# Sheet2.net
KiCad netlist of a schematic drawn in Altium Designer
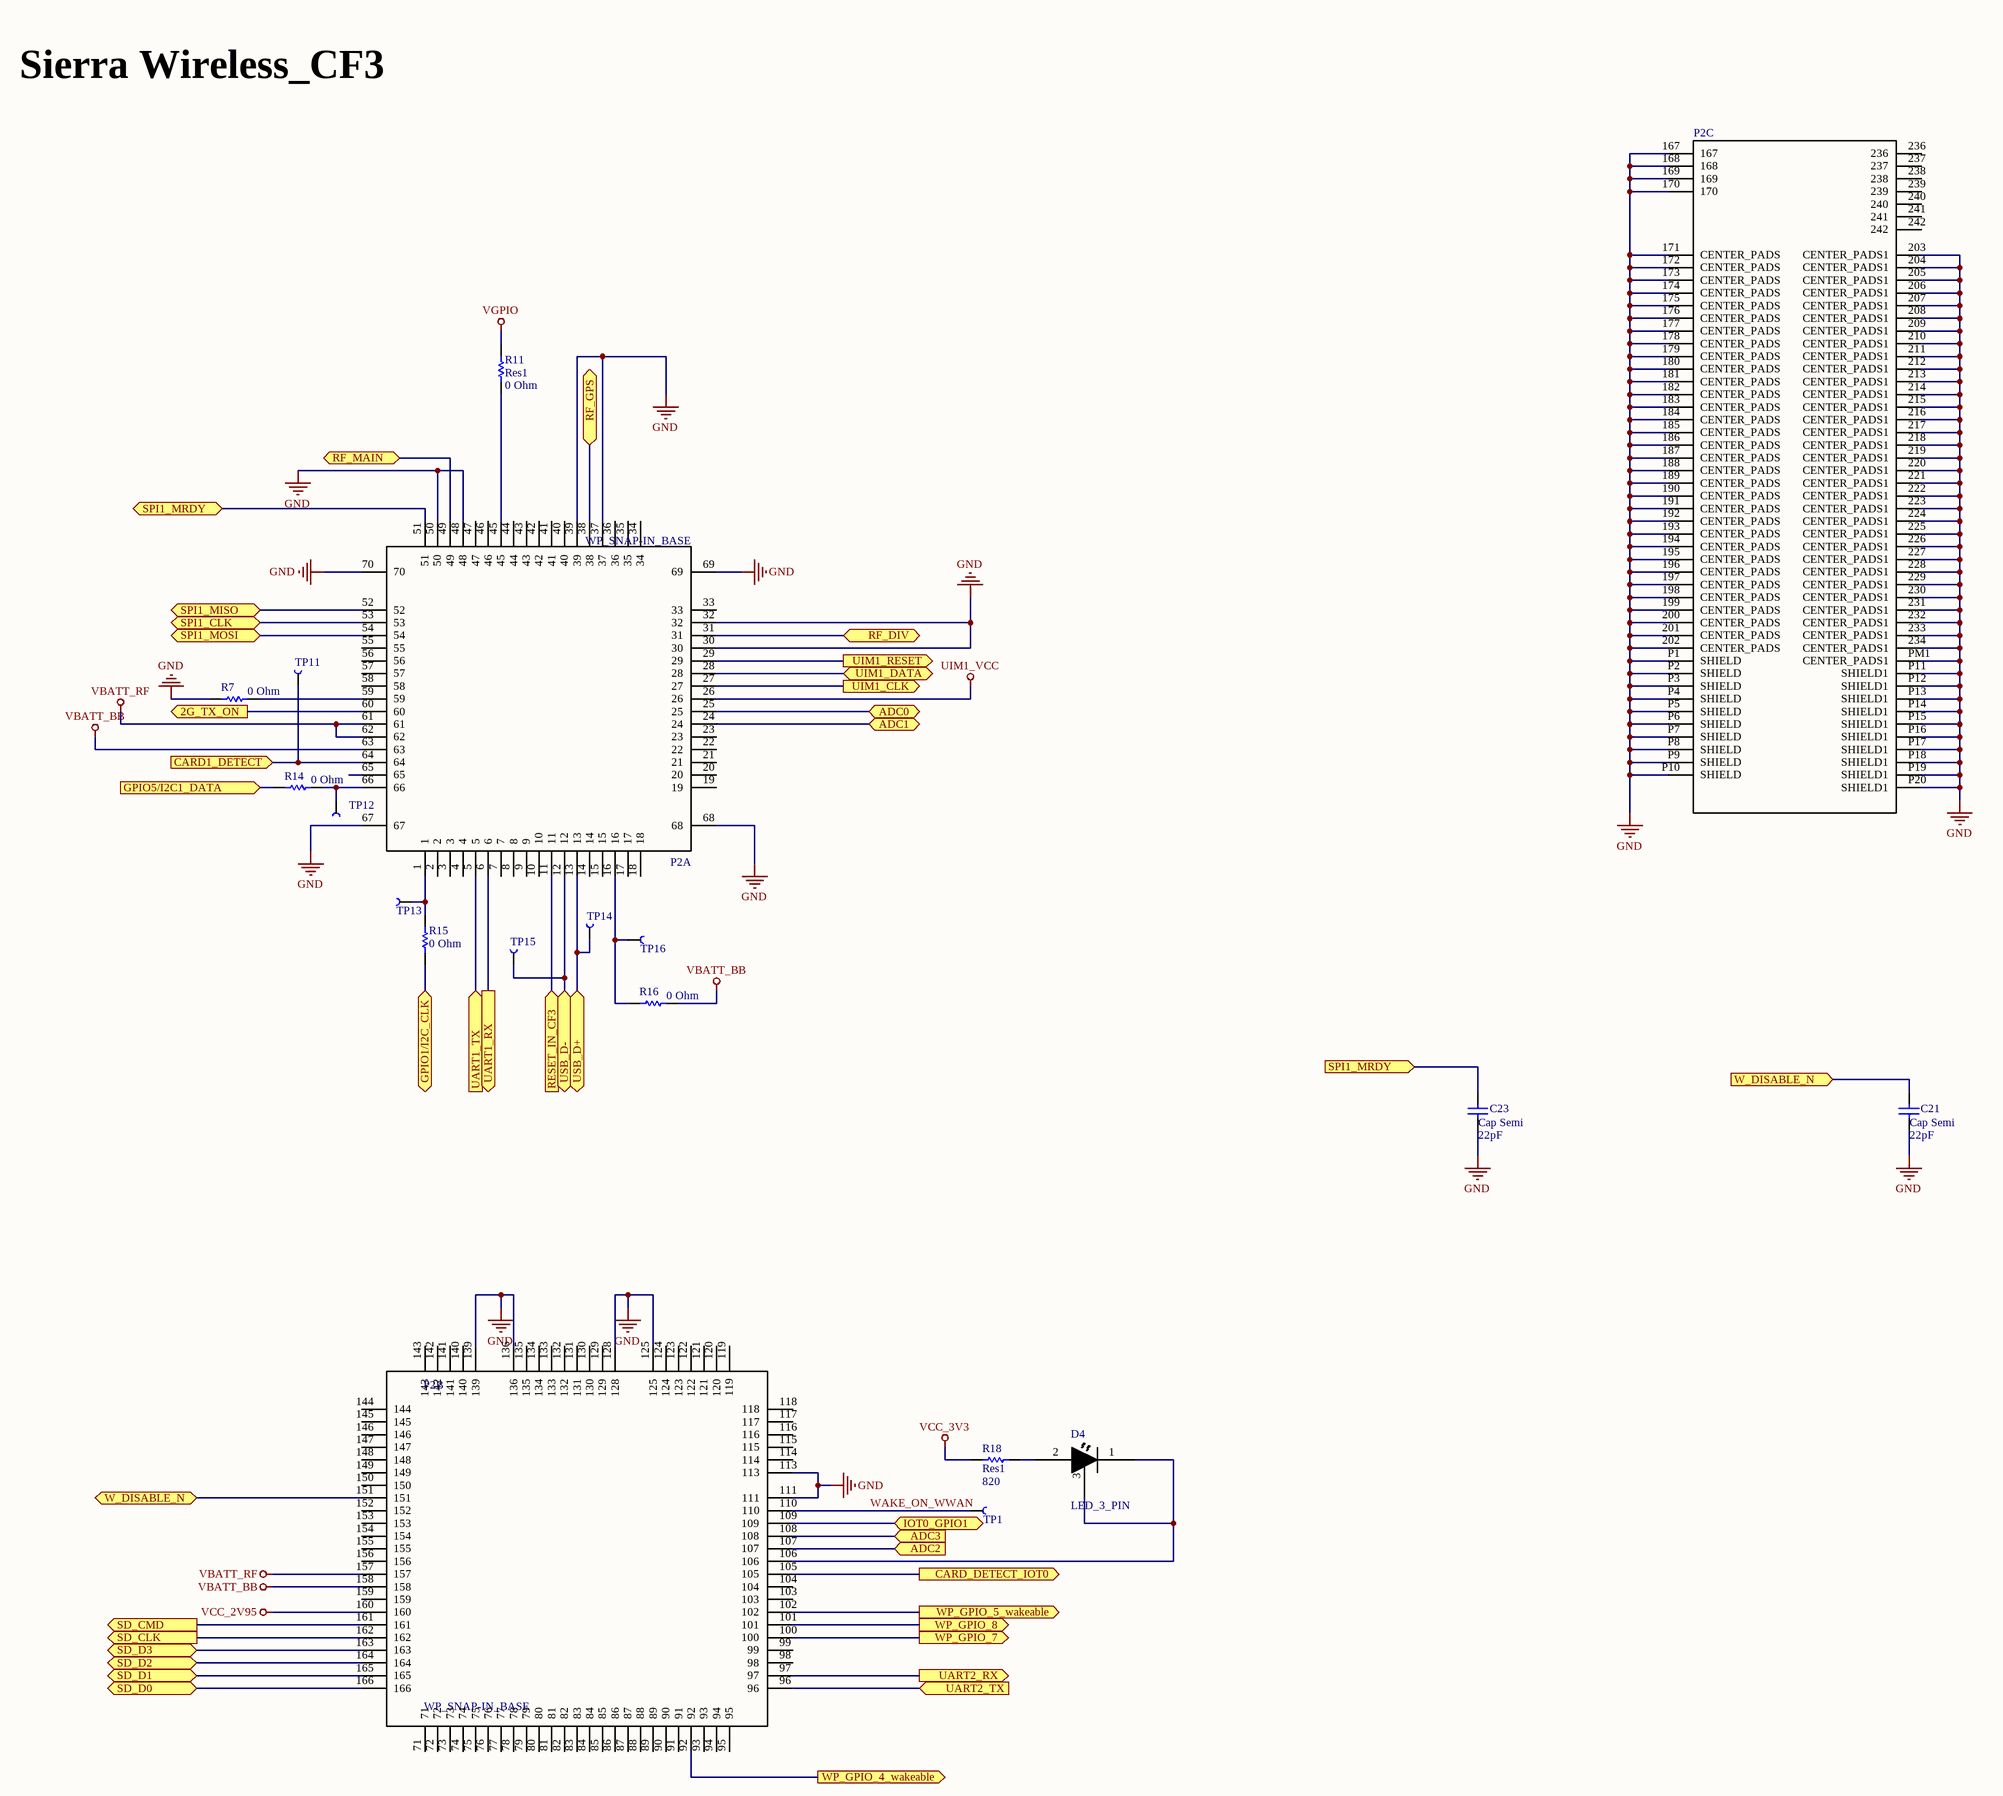
[diagram p0: Sheet2.SchDoc]

(export (version "E")
  (design (tool "Eeschema 10.0.6"))
  (components
    (comp (ref "C21")
      (value "Cap Semi")
      (footprint "CAP 0402/1005")
      (description "CAP CER 22PF 50V NP0 0402")
      (fields (field (name "PART NUMBER") "UMK105CG220JV-F") (field (name "ALTIUM_VALUE") "22pF"))
      (libsource (lib "Miscellaneous Devices") (part "Cap Semi"))
    )
    (comp (ref "C23")
      (value "Cap Semi")
      (footprint "CAP 0402/1005")
      (description "CAP CER 22PF 50V NP0 0402")
      (fields (field (name "PART NUMBER") "UMK105CG220JV-F") (field (name "ALTIUM_VALUE") "22pF"))
      (libsource (lib "Miscellaneous Devices") (part "Cap Semi"))
    )
    (comp (ref "D4")
      (value "LED_3_PIN")
      (footprint "LED_3_PIN")
      (description "Yellow-Green 573nm LED Indication - Discrete 2V 2-SMD, No Lead")
      (fields (field (name "PART NUMBER") "12-21SYGC/S530-E2/TR8"))
      (libsource (lib "LED_3_PIN") (part "LED_3_PIN"))
    )
    (comp (ref "P2")
      (value "WP_SNAP-IN_BASE")
      (footprint "*SIERRA_WP_SNAP-IN_BASE_WP_SNAP-IN_BASE(Primary)")
      (description "Snap-In Socket Base For Wp Series Mcu")
      (fields (field (name "PART NUMBER") "WP SNAP-IN BASE") (field (name "MF") "Sierra Wireless"))
      (libsource (lib "WP_SNAP-IN_BASE") (part "WP_SNAP-IN_BASE"))
    )
    (comp (ref "R7")
      (value "0 Ohm")
      (footprint "RES 0402/1005")
      (description "0 Ohms Jumper  Chip Resistor 0402 (1005 Metric) Automotive AEC-Q200 Metal Element")
      (fields (field (name "PART NUMBER") "RK73Z1ETTP") (field (name "Comment") "Res1"))
      (libsource (lib "Miscellaneous Devices") (part "Res1"))
    )
    (comp (ref "R11")
      (value "Res1")
      (footprint "RES 0402/1005")
      (description "0 Ohms Jumper  Chip Resistor 0402 (1005 Metric) Automotive AEC-Q200 Metal Element")
      (fields (field (name "PART NUMBER") "RK73Z1ETTP") (field (name "ALTIUM_VALUE") "0 Ohm"))
      (libsource (lib "Miscellaneous Devices") (part "Res1"))
    )
    (comp (ref "R14")
      (value "0 Ohm")
      (footprint "RES 0402/1005")
      (description "0 Ohms Jumper  Chip Resistor 0402 (1005 Metric) Automotive AEC-Q200 Metal Element")
      (fields (field (name "PART NUMBER") "RK73Z1ETTP") (field (name "Comment") "Res1"))
      (libsource (lib "Miscellaneous Devices") (part "Res1"))
    )
    (comp (ref "R15")
      (value "0 Ohm")
      (footprint "RES 0402/1005")
      (description "0 Ohms Jumper  Chip Resistor 0402 (1005 Metric) Automotive AEC-Q200 Metal Element")
      (fields (field (name "PART NUMBER") "RK73Z1ETTP") (field (name "Comment") "Res1"))
      (libsource (lib "Miscellaneous Devices") (part "Res1"))
    )
    (comp (ref "R16")
      (value "0 Ohm")
      (footprint "RES 0402/1005")
      (description "0 Ohms Jumper  Chip Resistor 0402 (1005 Metric) Automotive AEC-Q200 Metal Element")
      (fields (field (name "PART NUMBER") "RK73Z1ETTP") (field (name "Comment") "Res1"))
      (libsource (lib "Miscellaneous Devices") (part "Res1"))
    )
    (comp (ref "R18")
      (value "Res1")
      (footprint "RES 0402/1005")
      (description "820 Ohms ±5% 0.1W, 1/10W Chip Resistor 0402 (1005 Metric) Automotive AEC-Q200 Thick Film")
      (fields (field (name "PART NUMBER") "RK73B1ETTP821J") (field (name "ALTIUM_VALUE") "820"))
      (libsource (lib "Miscellaneous Devices") (part "Res1"))
    )
    (comp (ref "TP1")
      (value "TestPoint")
      (footprint "TestPoint")
      (libsource (lib "TestPoint") (part "TestPoint"))
    )
    (comp (ref "TP11")
      (value "TestPoint")
      (footprint "TestPoint")
      (libsource (lib "TestPoint") (part "TestPoint"))
    )
    (comp (ref "TP12")
      (value "TestPoint")
      (footprint "TestPoint")
      (libsource (lib "TestPoint") (part "TestPoint"))
    )
    (comp (ref "TP13")
      (value "TestPoint")
      (footprint "TestPoint")
      (libsource (lib "TestPoint") (part "TestPoint"))
    )
    (comp (ref "TP14")
      (value "TestPoint")
      (footprint "TestPoint")
      (libsource (lib "TestPoint") (part "TestPoint"))
    )
    (comp (ref "TP15")
      (value "TestPoint")
      (footprint "TestPoint")
      (libsource (lib "TestPoint") (part "TestPoint"))
    )
    (comp (ref "TP16")
      (value "TestPoint")
      (footprint "TestPoint")
      (libsource (lib "TestPoint") (part "TestPoint"))
    )
  )
  (nets
    (net (code "1") (name "/2G_TX_ON") (class "Default")
      (node (ref "P2") (pin "60") (pinfunction "60_60") (pintype "passive"))
    )
    (net (code "2") (name "/ADC0") (class "Default")
      (node (ref "P2") (pin "25") (pinfunction "25_25") (pintype "passive"))
    )
    (net (code "3") (name "/ADC1") (class "Default")
      (node (ref "P2") (pin "24") (pinfunction "24_24") (pintype "passive"))
    )
    (net (code "4") (name "/ADC2") (class "Default")
      (node (ref "P2") (pin "107") (pinfunction "107_107") (pintype "passive"))
    )
    (net (code "5") (name "/ADC3") (class "Default")
      (node (ref "P2") (pin "108") (pinfunction "108_108") (pintype "passive"))
    )
    (net (code "6") (name "/CARD1_DETECT") (class "Default")
      (node (ref "P2") (pin "64") (pinfunction "64_64") (pintype "passive"))
      (node (ref "TP11") (pin "1") (pinfunction "TP_1") (pintype "passive"))
    )
    (net (code "7") (name "/CARD_DETECT_IOT0") (class "Default")
      (node (ref "P2") (pin "105") (pinfunction "105_105") (pintype "passive"))
    )
    (net (code "8") (name "/GPIO1{slash}I2C_CLK") (class "Default")
      (node (ref "R15") (pin "2") (pinfunction "2_2") (pintype "passive"))
    )
    (net (code "9") (name "/GPIO5{slash}I2C1_DATA") (class "Default")
      (node (ref "R14") (pin "2") (pinfunction "2_2") (pintype "passive"))
    )
    (net (code "10") (name "/IOT0_GPIO1") (class "Default")
      (node (ref "P2") (pin "109") (pinfunction "109_109") (pintype "passive"))
    )
    (net (code "11") (name "/RESET_IN_CF3") (class "Default")
      (node (ref "P2") (pin "11") (pinfunction "11_11") (pintype "passive"))
    )
    (net (code "12") (name "/RF_DIV") (class "Default")
      (node (ref "P2") (pin "31") (pinfunction "31_31") (pintype "passive"))
    )
    (net (code "13") (name "/RF_GPS") (class "Default")
      (node (ref "P2") (pin "38") (pinfunction "38_38") (pintype "passive"))
    )
    (net (code "14") (name "/RF_MAIN") (class "Default")
      (node (ref "P2") (pin "49") (pinfunction "49_49") (pintype "passive"))
    )
    (net (code "15") (name "/SD_CLK") (class "Default")
      (node (ref "P2") (pin "162") (pinfunction "162_162") (pintype "passive"))
    )
    (net (code "16") (name "/SD_CMD") (class "Default")
      (node (ref "P2") (pin "161") (pinfunction "161_161") (pintype "passive"))
    )
    (net (code "17") (name "/SD_D0") (class "Default")
      (node (ref "P2") (pin "166") (pinfunction "166_166") (pintype "passive"))
    )
    (net (code "18") (name "/SD_D1") (class "Default")
      (node (ref "P2") (pin "165") (pinfunction "165_165") (pintype "passive"))
    )
    (net (code "19") (name "/SD_D2") (class "Default")
      (node (ref "P2") (pin "164") (pinfunction "164_164") (pintype "passive"))
    )
    (net (code "20") (name "/SD_D3") (class "Default")
      (node (ref "P2") (pin "163") (pinfunction "163_163") (pintype "passive"))
    )
    (net (code "21") (name "/SPI1_CLK") (class "Default")
      (node (ref "P2") (pin "53") (pinfunction "53_53") (pintype "passive"))
    )
    (net (code "22") (name "/SPI1_MISO") (class "Default")
      (node (ref "P2") (pin "52") (pinfunction "52_52") (pintype "passive"))
    )
    (net (code "23") (name "/SPI1_MOSI") (class "Default")
      (node (ref "P2") (pin "54") (pinfunction "54_54") (pintype "passive"))
    )
    (net (code "24") (name "/SPI1_MRDY") (class "Default")
      (node (ref "C23") (pin "2") (pinfunction "2_2") (pintype "passive"))
      (node (ref "P2") (pin "51") (pinfunction "51_51") (pintype "passive"))
    )
    (net (code "25") (name "/UART1_RX") (class "Default")
      (node (ref "P2") (pin "6") (pinfunction "6_6") (pintype "passive"))
    )
    (net (code "26") (name "/UART1_TX") (class "Default")
      (node (ref "P2") (pin "5") (pinfunction "5_5") (pintype "passive"))
    )
    (net (code "27") (name "/UART2_RX") (class "Default")
      (node (ref "P2") (pin "97") (pinfunction "97_97") (pintype "passive"))
    )
    (net (code "28") (name "/UART2_TX") (class "Default")
      (node (ref "P2") (pin "96") (pinfunction "96_96") (pintype "passive"))
    )
    (net (code "29") (name "/UIM1_CLK") (class "Default")
      (node (ref "P2") (pin "27") (pinfunction "27_27") (pintype "passive"))
    )
    (net (code "30") (name "/UIM1_DATA") (class "Default")
      (node (ref "P2") (pin "28") (pinfunction "28_28") (pintype "passive"))
    )
    (net (code "31") (name "/UIM1_RESET") (class "Default")
      (node (ref "P2") (pin "29") (pinfunction "29_29") (pintype "passive"))
    )
    (net (code "32") (name "/USB_D+") (class "Default")
      (node (ref "P2") (pin "13") (pinfunction "13_13") (pintype "passive"))
      (node (ref "TP14") (pin "1") (pinfunction "TP_1") (pintype "passive"))
    )
    (net (code "33") (name "/USB_D-") (class "Default")
      (node (ref "P2") (pin "12") (pinfunction "12_12") (pintype "passive"))
      (node (ref "TP15") (pin "1") (pinfunction "TP_1") (pintype "passive"))
    )
    (net (code "34") (name "/WAKE_ON_WWAN") (class "Default")
      (node (ref "P2") (pin "110") (pinfunction "110_110") (pintype "passive"))
      (node (ref "TP1") (pin "1") (pinfunction "TP_1") (pintype "passive"))
    )
    (net (code "35") (name "/WP_GPIO_4_wakeable") (class "Default")
      (node (ref "P2") (pin "92") (pinfunction "92_92") (pintype "passive"))
    )
    (net (code "36") (name "/WP_GPIO_5_wakeable") (class "Default")
      (node (ref "P2") (pin "102") (pinfunction "102_102") (pintype "passive"))
    )
    (net (code "37") (name "/WP_GPIO_7") (class "Default")
      (node (ref "P2") (pin "100") (pinfunction "100_100") (pintype "passive"))
    )
    (net (code "38") (name "/WP_GPIO_8") (class "Default")
      (node (ref "P2") (pin "101") (pinfunction "101_101") (pintype "passive"))
    )
    (net (code "39") (name "/W_DISABLE_N") (class "Default")
      (node (ref "C21") (pin "2") (pinfunction "2_2") (pintype "passive"))
      (node (ref "P2") (pin "151") (pinfunction "151_151") (pintype "passive"))
    )
    (net (code "40") (name "GND") (class "Default")
      (node (ref "C21") (pin "1") (pinfunction "1_1") (pintype "passive"))
      (node (ref "C23") (pin "1") (pinfunction "1_1") (pintype "passive"))
      (node (ref "P2") (pin "111") (pinfunction "111_111") (pintype "passive"))
      (node (ref "P2") (pin "113") (pinfunction "113_113") (pintype "passive"))
      (node (ref "P2") (pin "125") (pinfunction "125_125") (pintype "passive"))
      (node (ref "P2") (pin "128") (pinfunction "128_128") (pintype "passive"))
      (node (ref "P2") (pin "136") (pinfunction "136_136") (pintype "passive"))
      (node (ref "P2") (pin "139") (pinfunction "139_139") (pintype "passive"))
      (node (ref "P2") (pin "167") (pinfunction "167_167") (pintype "passive"))
      (node (ref "P2") (pin "168") (pinfunction "168_168") (pintype "passive"))
      (node (ref "P2") (pin "169") (pinfunction "169_169") (pintype "passive"))
      (node (ref "P2") (pin "170") (pinfunction "170_170") (pintype "passive"))
      (node (ref "P2") (pin "171") (pinfunction "CENTER_PADS_171") (pintype "passive"))
      (node (ref "P2") (pin "172") (pinfunction "CENTER_PADS_172") (pintype "passive"))
      (node (ref "P2") (pin "173") (pinfunction "CENTER_PADS_173") (pintype "passive"))
      (node (ref "P2") (pin "174") (pinfunction "CENTER_PADS_174") (pintype "passive"))
      (node (ref "P2") (pin "175") (pinfunction "CENTER_PADS_175") (pintype "passive"))
      (node (ref "P2") (pin "176") (pinfunction "CENTER_PADS_176") (pintype "passive"))
      (node (ref "P2") (pin "177") (pinfunction "CENTER_PADS_177") (pintype "passive"))
      (node (ref "P2") (pin "178") (pinfunction "CENTER_PADS_178") (pintype "passive"))
      (node (ref "P2") (pin "179") (pinfunction "CENTER_PADS_179") (pintype "passive"))
      (node (ref "P2") (pin "180") (pinfunction "CENTER_PADS_180") (pintype "passive"))
      (node (ref "P2") (pin "181") (pinfunction "CENTER_PADS_181") (pintype "passive"))
      (node (ref "P2") (pin "182") (pinfunction "CENTER_PADS_182") (pintype "passive"))
      (node (ref "P2") (pin "183") (pinfunction "CENTER_PADS_183") (pintype "passive"))
      (node (ref "P2") (pin "184") (pinfunction "CENTER_PADS_184") (pintype "passive"))
      (node (ref "P2") (pin "185") (pinfunction "CENTER_PADS_185") (pintype "passive"))
      (node (ref "P2") (pin "186") (pinfunction "CENTER_PADS_186") (pintype "passive"))
      (node (ref "P2") (pin "187") (pinfunction "CENTER_PADS_187") (pintype "passive"))
      (node (ref "P2") (pin "188") (pinfunction "CENTER_PADS_188") (pintype "passive"))
      (node (ref "P2") (pin "189") (pinfunction "CENTER_PADS_189") (pintype "passive"))
      (node (ref "P2") (pin "190") (pinfunction "CENTER_PADS_190") (pintype "passive"))
      (node (ref "P2") (pin "191") (pinfunction "CENTER_PADS_191") (pintype "passive"))
      (node (ref "P2") (pin "192") (pinfunction "CENTER_PADS_192") (pintype "passive"))
      (node (ref "P2") (pin "193") (pinfunction "CENTER_PADS_193") (pintype "passive"))
      (node (ref "P2") (pin "194") (pinfunction "CENTER_PADS_194") (pintype "passive"))
      (node (ref "P2") (pin "195") (pinfunction "CENTER_PADS_195") (pintype "passive"))
      (node (ref "P2") (pin "196") (pinfunction "CENTER_PADS_196") (pintype "passive"))
      (node (ref "P2") (pin "197") (pinfunction "CENTER_PADS_197") (pintype "passive"))
      (node (ref "P2") (pin "198") (pinfunction "CENTER_PADS_198") (pintype "passive"))
      (node (ref "P2") (pin "199") (pinfunction "CENTER_PADS_199") (pintype "passive"))
      (node (ref "P2") (pin "200") (pinfunction "CENTER_PADS_200") (pintype "passive"))
      (node (ref "P2") (pin "201") (pinfunction "CENTER_PADS_201") (pintype "passive"))
      (node (ref "P2") (pin "202") (pinfunction "CENTER_PADS_202") (pintype "passive"))
      (node (ref "P2") (pin "203") (pinfunction "CENTER_PADS1_203") (pintype "passive"))
      (node (ref "P2") (pin "204") (pinfunction "CENTER_PADS1_204") (pintype "passive"))
      (node (ref "P2") (pin "205") (pinfunction "CENTER_PADS1_205") (pintype "passive"))
      (node (ref "P2") (pin "206") (pinfunction "CENTER_PADS1_206") (pintype "passive"))
      (node (ref "P2") (pin "207") (pinfunction "CENTER_PADS1_207") (pintype "passive"))
      (node (ref "P2") (pin "208") (pinfunction "CENTER_PADS1_208") (pintype "passive"))
      (node (ref "P2") (pin "209") (pinfunction "CENTER_PADS1_209") (pintype "passive"))
      (node (ref "P2") (pin "210") (pinfunction "CENTER_PADS1_210") (pintype "passive"))
      (node (ref "P2") (pin "211") (pinfunction "CENTER_PADS1_211") (pintype "passive"))
      (node (ref "P2") (pin "212") (pinfunction "CENTER_PADS1_212") (pintype "passive"))
      (node (ref "P2") (pin "213") (pinfunction "CENTER_PADS1_213") (pintype "passive"))
      (node (ref "P2") (pin "214") (pinfunction "CENTER_PADS1_214") (pintype "passive"))
      (node (ref "P2") (pin "215") (pinfunction "CENTER_PADS1_215") (pintype "passive"))
      (node (ref "P2") (pin "216") (pinfunction "CENTER_PADS1_216") (pintype "passive"))
      (node (ref "P2") (pin "217") (pinfunction "CENTER_PADS1_217") (pintype "passive"))
      (node (ref "P2") (pin "218") (pinfunction "CENTER_PADS1_218") (pintype "passive"))
      (node (ref "P2") (pin "219") (pinfunction "CENTER_PADS1_219") (pintype "passive"))
      (node (ref "P2") (pin "220") (pinfunction "CENTER_PADS1_220") (pintype "passive"))
      (node (ref "P2") (pin "221") (pinfunction "CENTER_PADS1_221") (pintype "passive"))
      (node (ref "P2") (pin "222") (pinfunction "CENTER_PADS1_222") (pintype "passive"))
      (node (ref "P2") (pin "223") (pinfunction "CENTER_PADS1_223") (pintype "passive"))
      (node (ref "P2") (pin "224") (pinfunction "CENTER_PADS1_224") (pintype "passive"))
      (node (ref "P2") (pin "225") (pinfunction "CENTER_PADS1_225") (pintype "passive"))
      (node (ref "P2") (pin "226") (pinfunction "CENTER_PADS1_226") (pintype "passive"))
      (node (ref "P2") (pin "227") (pinfunction "CENTER_PADS1_227") (pintype "passive"))
      (node (ref "P2") (pin "228") (pinfunction "CENTER_PADS1_228") (pintype "passive"))
      (node (ref "P2") (pin "229") (pinfunction "CENTER_PADS1_229") (pintype "passive"))
      (node (ref "P2") (pin "230") (pinfunction "CENTER_PADS1_230") (pintype "passive"))
      (node (ref "P2") (pin "231") (pinfunction "CENTER_PADS1_231") (pintype "passive"))
      (node (ref "P2") (pin "232") (pinfunction "CENTER_PADS1_232") (pintype "passive"))
      (node (ref "P2") (pin "233") (pinfunction "CENTER_PADS1_233") (pintype "passive"))
      (node (ref "P2") (pin "234") (pinfunction "CENTER_PADS1_234") (pintype "passive"))
      (node (ref "P2") (pin "30") (pinfunction "30_30") (pintype "passive"))
      (node (ref "P2") (pin "32") (pinfunction "32_32") (pintype "passive"))
      (node (ref "P2") (pin "37") (pinfunction "37_37") (pintype "passive"))
      (node (ref "P2") (pin "39") (pinfunction "39_39") (pintype "passive"))
      (node (ref "P2") (pin "48") (pinfunction "48_48") (pintype "passive"))
      (node (ref "P2") (pin "50") (pinfunction "50_50") (pintype "passive"))
      (node (ref "P2") (pin "67") (pinfunction "67_67") (pintype "passive"))
      (node (ref "P2") (pin "68") (pinfunction "68_68") (pintype "passive"))
      (node (ref "P2") (pin "69") (pinfunction "69_69") (pintype "passive"))
      (node (ref "P2") (pin "70") (pinfunction "70_70") (pintype "passive"))
      (node (ref "P2") (pin "P1") (pinfunction "SHIELD_P1") (pintype "passive"))
      (node (ref "P2") (pin "P10") (pinfunction "SHIELD_P10") (pintype "passive"))
      (node (ref "P2") (pin "P11") (pinfunction "SHIELD1_P11") (pintype "passive"))
      (node (ref "P2") (pin "P12") (pinfunction "SHIELD1_P12") (pintype "passive"))
      (node (ref "P2") (pin "P13") (pinfunction "SHIELD1_P13") (pintype "passive"))
      (node (ref "P2") (pin "P14") (pinfunction "SHIELD1_P14") (pintype "passive"))
      (node (ref "P2") (pin "P15") (pinfunction "SHIELD1_P15") (pintype "passive"))
      (node (ref "P2") (pin "P16") (pinfunction "SHIELD1_P16") (pintype "passive"))
      (node (ref "P2") (pin "P17") (pinfunction "SHIELD1_P17") (pintype "passive"))
      (node (ref "P2") (pin "P18") (pinfunction "SHIELD1_P18") (pintype "passive"))
      (node (ref "P2") (pin "P19") (pinfunction "SHIELD1_P19") (pintype "passive"))
      (node (ref "P2") (pin "P2") (pinfunction "SHIELD_P2") (pintype "passive"))
      (node (ref "P2") (pin "P20") (pinfunction "SHIELD1_P20") (pintype "passive"))
      (node (ref "P2") (pin "P3") (pinfunction "SHIELD_P3") (pintype "passive"))
      (node (ref "P2") (pin "P4") (pinfunction "SHIELD_P4") (pintype "passive"))
      (node (ref "P2") (pin "P5") (pinfunction "SHIELD_P5") (pintype "passive"))
      (node (ref "P2") (pin "P6") (pinfunction "SHIELD_P6") (pintype "passive"))
      (node (ref "P2") (pin "P7") (pinfunction "SHIELD_P7") (pintype "passive"))
      (node (ref "P2") (pin "P8") (pinfunction "SHIELD_P8") (pintype "passive"))
      (node (ref "P2") (pin "P9") (pinfunction "SHIELD_P9") (pintype "passive"))
      (node (ref "P2") (pin "PM1") (pinfunction "CENTER_PADS1_PM1") (pintype "passive"))
      (node (ref "R7") (pin "2") (pinfunction "2_2") (pintype "passive"))
    )
    (net (code "41") (name "Net-(D4-Pad1)") (class "Default")
      (node (ref "D4") (pin "1") (pintype "passive"))
      (node (ref "D4") (pin "3") (pintype "passive"))
      (node (ref "P2") (pin "106") (pinfunction "106_106") (pintype "passive"))
    )
    (net (code "42") (name "Net-(D4-Pad2)") (class "Default")
      (node (ref "D4") (pin "2") (pintype "passive"))
      (node (ref "R18") (pin "1") (pinfunction "1_1") (pintype "passive"))
    )
    (net (code "43") (name "Net-(P2-Pad45)") (class "Default")
      (node (ref "P2") (pin "45") (pinfunction "45_45") (pintype "passive"))
      (node (ref "R11") (pin "2") (pinfunction "2_2") (pintype "passive"))
    )
    (net (code "44") (name "Net-(P2-Pad59)") (class "Default")
      (node (ref "P2") (pin "59") (pinfunction "59_59") (pintype "passive"))
      (node (ref "R7") (pin "1") (pinfunction "1_1") (pintype "passive"))
    )
    (net (code "45") (name "Net-(TP12-TP)") (class "Default")
      (node (ref "P2") (pin "66") (pinfunction "66_66") (pintype "passive"))
      (node (ref "R14") (pin "1") (pinfunction "1_1") (pintype "passive"))
      (node (ref "TP12") (pin "1") (pinfunction "TP_1") (pintype "passive"))
    )
    (net (code "46") (name "Net-(TP13-TP)") (class "Default")
      (node (ref "P2") (pin "1") (pinfunction "1_1") (pintype "passive"))
      (node (ref "R15") (pin "1") (pinfunction "1_1") (pintype "passive"))
      (node (ref "TP13") (pin "1") (pinfunction "TP_1") (pintype "passive"))
    )
    (net (code "47") (name "Net-(TP16-TP)") (class "Default")
      (node (ref "P2") (pin "16") (pinfunction "16_16") (pintype "passive"))
      (node (ref "R16") (pin "2") (pinfunction "2_2") (pintype "passive"))
      (node (ref "TP16") (pin "1") (pinfunction "TP_1") (pintype "passive"))
    )
    (net (code "48") (name "UIM1_VCC") (class "Default")
      (node (ref "P2") (pin "26") (pinfunction "26_26") (pintype "passive"))
    )
    (net (code "49") (name "VBATT_BB") (class "Default")
      (node (ref "P2") (pin "158") (pinfunction "158_158") (pintype "passive"))
      (node (ref "P2") (pin "63") (pinfunction "63_63") (pintype "passive"))
      (node (ref "R16") (pin "1") (pinfunction "1_1") (pintype "passive"))
    )
    (net (code "50") (name "VBATT_RF") (class "Default")
      (node (ref "P2") (pin "157") (pinfunction "157_157") (pintype "passive"))
      (node (ref "P2") (pin "61") (pinfunction "61_61") (pintype "passive"))
      (node (ref "P2") (pin "62") (pinfunction "62_62") (pintype "passive"))
    )
    (net (code "51") (name "VCC_2V95") (class "Default")
      (node (ref "P2") (pin "160") (pinfunction "160_160") (pintype "passive"))
    )
    (net (code "52") (name "VCC_3V3") (class "Default")
      (node (ref "R18") (pin "2") (pinfunction "2_2") (pintype "passive"))
    )
    (net (code "53") (name "VGPIO") (class "Default")
      (node (ref "R11") (pin "1") (pinfunction "1_1") (pintype "passive"))
    )
    (net (code "54") (name "unconnected-(P2-Pad2)") (class "Default")
      (node (ref "P2") (pin "2") (pinfunction "2_2") (pintype "passive"))
    )
    (net (code "55") (name "unconnected-(P2-Pad3)") (class "Default")
      (node (ref "P2") (pin "3") (pinfunction "3_3") (pintype "passive"))
    )
    (net (code "56") (name "unconnected-(P2-Pad4)") (class "Default")
      (node (ref "P2") (pin "4") (pinfunction "4_4") (pintype "passive"))
    )
    (net (code "57") (name "unconnected-(P2-Pad7)") (class "Default")
      (node (ref "P2") (pin "7") (pinfunction "7_7") (pintype "passive"))
    )
    (net (code "58") (name "unconnected-(P2-Pad8)") (class "Default")
      (node (ref "P2") (pin "8") (pinfunction "8_8") (pintype "passive"))
    )
    (net (code "59") (name "unconnected-(P2-Pad9)") (class "Default")
      (node (ref "P2") (pin "9") (pinfunction "9_9") (pintype "passive"))
    )
    (net (code "60") (name "unconnected-(P2-Pad10)") (class "Default")
      (node (ref "P2") (pin "10") (pinfunction "10_10") (pintype "passive"))
    )
    (net (code "61") (name "unconnected-(P2-Pad14)") (class "Default")
      (node (ref "P2") (pin "14") (pinfunction "14_14") (pintype "passive"))
    )
    (net (code "62") (name "unconnected-(P2-Pad15)") (class "Default")
      (node (ref "P2") (pin "15") (pinfunction "15_15") (pintype "passive"))
    )
    (net (code "63") (name "unconnected-(P2-Pad17)") (class "Default")
      (node (ref "P2") (pin "17") (pinfunction "17_17") (pintype "passive"))
    )
    (net (code "64") (name "unconnected-(P2-Pad18)") (class "Default")
      (node (ref "P2") (pin "18") (pinfunction "18_18") (pintype "passive"))
    )
    (net (code "65") (name "unconnected-(P2-Pad19)") (class "Default")
      (node (ref "P2") (pin "19") (pinfunction "19_19") (pintype "passive"))
    )
    (net (code "66") (name "unconnected-(P2-Pad20)") (class "Default")
      (node (ref "P2") (pin "20") (pinfunction "20_20") (pintype "passive"))
    )
    (net (code "67") (name "unconnected-(P2-Pad21)") (class "Default")
      (node (ref "P2") (pin "21") (pinfunction "21_21") (pintype "passive"))
    )
    (net (code "68") (name "unconnected-(P2-Pad22)") (class "Default")
      (node (ref "P2") (pin "22") (pinfunction "22_22") (pintype "passive"))
    )
    (net (code "69") (name "unconnected-(P2-Pad23)") (class "Default")
      (node (ref "P2") (pin "23") (pinfunction "23_23") (pintype "passive"))
    )
    (net (code "70") (name "unconnected-(P2-Pad33)") (class "Default")
      (node (ref "P2") (pin "33") (pinfunction "33_33") (pintype "passive"))
    )
    (net (code "71") (name "unconnected-(P2-Pad34)") (class "Default")
      (node (ref "P2") (pin "34") (pinfunction "34_34") (pintype "passive"))
    )
    (net (code "72") (name "unconnected-(P2-Pad35)") (class "Default")
      (node (ref "P2") (pin "35") (pinfunction "35_35") (pintype "passive"))
    )
    (net (code "73") (name "unconnected-(P2-Pad36)") (class "Default")
      (node (ref "P2") (pin "36") (pinfunction "36_36") (pintype "passive"))
    )
    (net (code "74") (name "unconnected-(P2-Pad40)") (class "Default")
      (node (ref "P2") (pin "40") (pinfunction "40_40") (pintype "passive"))
    )
    (net (code "75") (name "unconnected-(P2-Pad41)") (class "Default")
      (node (ref "P2") (pin "41") (pinfunction "41_41") (pintype "passive"))
    )
    (net (code "76") (name "unconnected-(P2-Pad42)") (class "Default")
      (node (ref "P2") (pin "42") (pinfunction "42_42") (pintype "passive"))
    )
    (net (code "77") (name "unconnected-(P2-Pad43)") (class "Default")
      (node (ref "P2") (pin "43") (pinfunction "43_43") (pintype "passive"))
    )
    (net (code "78") (name "unconnected-(P2-Pad44)") (class "Default")
      (node (ref "P2") (pin "44") (pinfunction "44_44") (pintype "passive"))
    )
    (net (code "79") (name "unconnected-(P2-Pad46)") (class "Default")
      (node (ref "P2") (pin "46") (pinfunction "46_46") (pintype "passive"))
    )
    (net (code "80") (name "unconnected-(P2-Pad47)") (class "Default")
      (node (ref "P2") (pin "47") (pinfunction "47_47") (pintype "passive"))
    )
    (net (code "81") (name "unconnected-(P2-Pad55)") (class "Default")
      (node (ref "P2") (pin "55") (pinfunction "55_55") (pintype "passive"))
    )
    (net (code "82") (name "unconnected-(P2-Pad56)") (class "Default")
      (node (ref "P2") (pin "56") (pinfunction "56_56") (pintype "passive"))
    )
    (net (code "83") (name "unconnected-(P2-Pad57)") (class "Default")
      (node (ref "P2") (pin "57") (pinfunction "57_57") (pintype "passive"))
    )
    (net (code "84") (name "unconnected-(P2-Pad58)") (class "Default")
      (node (ref "P2") (pin "58") (pinfunction "58_58") (pintype "passive"))
    )
    (net (code "85") (name "unconnected-(P2-Pad65)") (class "Default")
      (node (ref "P2") (pin "65") (pinfunction "65_65") (pintype "passive"))
    )
    (net (code "86") (name "unconnected-(P2-Pad71)") (class "Default")
      (node (ref "P2") (pin "71") (pinfunction "71_71") (pintype "passive"))
    )
    (net (code "87") (name "unconnected-(P2-Pad72)") (class "Default")
      (node (ref "P2") (pin "72") (pinfunction "72_72") (pintype "passive"))
    )
    (net (code "88") (name "unconnected-(P2-Pad73)") (class "Default")
      (node (ref "P2") (pin "73") (pinfunction "73_73") (pintype "passive"))
    )
    (net (code "89") (name "unconnected-(P2-Pad74)") (class "Default")
      (node (ref "P2") (pin "74") (pinfunction "74_74") (pintype "passive"))
    )
    (net (code "90") (name "unconnected-(P2-Pad75)") (class "Default")
      (node (ref "P2") (pin "75") (pinfunction "75_75") (pintype "passive"))
    )
    (net (code "91") (name "unconnected-(P2-Pad76)") (class "Default")
      (node (ref "P2") (pin "76") (pinfunction "76_76") (pintype "passive"))
    )
    (net (code "92") (name "unconnected-(P2-Pad77)") (class "Default")
      (node (ref "P2") (pin "77") (pinfunction "77_77") (pintype "passive"))
    )
    (net (code "93") (name "unconnected-(P2-Pad78)") (class "Default")
      (node (ref "P2") (pin "78") (pinfunction "78_78") (pintype "passive"))
    )
    (net (code "94") (name "unconnected-(P2-Pad79)") (class "Default")
      (node (ref "P2") (pin "79") (pinfunction "79_79") (pintype "passive"))
    )
    (net (code "95") (name "unconnected-(P2-Pad80)") (class "Default")
      (node (ref "P2") (pin "80") (pinfunction "80_80") (pintype "passive"))
    )
    (net (code "96") (name "unconnected-(P2-Pad81)") (class "Default")
      (node (ref "P2") (pin "81") (pinfunction "81_81") (pintype "passive"))
    )
    (net (code "97") (name "unconnected-(P2-Pad82)") (class "Default")
      (node (ref "P2") (pin "82") (pinfunction "82_82") (pintype "passive"))
    )
    (net (code "98") (name "unconnected-(P2-Pad83)") (class "Default")
      (node (ref "P2") (pin "83") (pinfunction "83_83") (pintype "passive"))
    )
    (net (code "99") (name "unconnected-(P2-Pad84)") (class "Default")
      (node (ref "P2") (pin "84") (pinfunction "84_84") (pintype "passive"))
    )
    (net (code "100") (name "unconnected-(P2-Pad85)") (class "Default")
      (node (ref "P2") (pin "85") (pinfunction "85_85") (pintype "passive"))
    )
    (net (code "101") (name "unconnected-(P2-Pad86)") (class "Default")
      (node (ref "P2") (pin "86") (pinfunction "86_86") (pintype "passive"))
    )
    (net (code "102") (name "unconnected-(P2-Pad87)") (class "Default")
      (node (ref "P2") (pin "87") (pinfunction "87_87") (pintype "passive"))
    )
    (net (code "103") (name "unconnected-(P2-Pad88)") (class "Default")
      (node (ref "P2") (pin "88") (pinfunction "88_88") (pintype "passive"))
    )
    (net (code "104") (name "unconnected-(P2-Pad89)") (class "Default")
      (node (ref "P2") (pin "89") (pinfunction "89_89") (pintype "passive"))
    )
    (net (code "105") (name "unconnected-(P2-Pad90)") (class "Default")
      (node (ref "P2") (pin "90") (pinfunction "90_90") (pintype "passive"))
    )
    (net (code "106") (name "unconnected-(P2-Pad91)") (class "Default")
      (node (ref "P2") (pin "91") (pinfunction "91_91") (pintype "passive"))
    )
    (net (code "107") (name "unconnected-(P2-Pad93)") (class "Default")
      (node (ref "P2") (pin "93") (pinfunction "93_93") (pintype "passive"))
    )
    (net (code "108") (name "unconnected-(P2-Pad94)") (class "Default")
      (node (ref "P2") (pin "94") (pinfunction "94_94") (pintype "passive"))
    )
    (net (code "109") (name "unconnected-(P2-Pad95)") (class "Default")
      (node (ref "P2") (pin "95") (pinfunction "95_95") (pintype "passive"))
    )
    (net (code "110") (name "unconnected-(P2-Pad98)") (class "Default")
      (node (ref "P2") (pin "98") (pinfunction "98_98") (pintype "passive"))
    )
    (net (code "111") (name "unconnected-(P2-Pad99)") (class "Default")
      (node (ref "P2") (pin "99") (pinfunction "99_99") (pintype "passive"))
    )
    (net (code "112") (name "unconnected-(P2-Pad103)") (class "Default")
      (node (ref "P2") (pin "103") (pinfunction "103_103") (pintype "passive"))
    )
    (net (code "113") (name "unconnected-(P2-Pad104)") (class "Default")
      (node (ref "P2") (pin "104") (pinfunction "104_104") (pintype "passive"))
    )
    (net (code "114") (name "unconnected-(P2-Pad114)") (class "Default")
      (node (ref "P2") (pin "114") (pinfunction "114_114") (pintype "passive"))
    )
    (net (code "115") (name "unconnected-(P2-Pad115)") (class "Default")
      (node (ref "P2") (pin "115") (pinfunction "115_115") (pintype "passive"))
    )
    (net (code "116") (name "unconnected-(P2-Pad116)") (class "Default")
      (node (ref "P2") (pin "116") (pinfunction "116_116") (pintype "passive"))
    )
    (net (code "117") (name "unconnected-(P2-Pad117)") (class "Default")
      (node (ref "P2") (pin "117") (pinfunction "117_117") (pintype "passive"))
    )
    (net (code "118") (name "unconnected-(P2-Pad118)") (class "Default")
      (node (ref "P2") (pin "118") (pinfunction "118_118") (pintype "passive"))
    )
    (net (code "119") (name "unconnected-(P2-Pad119)") (class "Default")
      (node (ref "P2") (pin "119") (pinfunction "119_119") (pintype "passive"))
    )
    (net (code "120") (name "unconnected-(P2-Pad120)") (class "Default")
      (node (ref "P2") (pin "120") (pinfunction "120_120") (pintype "passive"))
    )
    (net (code "121") (name "unconnected-(P2-Pad121)") (class "Default")
      (node (ref "P2") (pin "121") (pinfunction "121_121") (pintype "passive"))
    )
    (net (code "122") (name "unconnected-(P2-Pad122)") (class "Default")
      (node (ref "P2") (pin "122") (pinfunction "122_122") (pintype "passive"))
    )
    (net (code "123") (name "unconnected-(P2-Pad123)") (class "Default")
      (node (ref "P2") (pin "123") (pinfunction "123_123") (pintype "passive"))
    )
    (net (code "124") (name "unconnected-(P2-Pad124)") (class "Default")
      (node (ref "P2") (pin "124") (pinfunction "124_124") (pintype "passive"))
    )
    (net (code "125") (name "unconnected-(P2-Pad129)") (class "Default")
      (node (ref "P2") (pin "129") (pinfunction "129_129") (pintype "passive"))
    )
    (net (code "126") (name "unconnected-(P2-Pad130)") (class "Default")
      (node (ref "P2") (pin "130") (pinfunction "130_130") (pintype "passive"))
    )
    (net (code "127") (name "unconnected-(P2-Pad131)") (class "Default")
      (node (ref "P2") (pin "131") (pinfunction "131_131") (pintype "passive"))
    )
    (net (code "128") (name "unconnected-(P2-Pad132)") (class "Default")
      (node (ref "P2") (pin "132") (pinfunction "132_132") (pintype "passive"))
    )
    (net (code "129") (name "unconnected-(P2-Pad133)") (class "Default")
      (node (ref "P2") (pin "133") (pinfunction "133_133") (pintype "passive"))
    )
    (net (code "130") (name "unconnected-(P2-Pad134)") (class "Default")
      (node (ref "P2") (pin "134") (pinfunction "134_134") (pintype "passive"))
    )
    (net (code "131") (name "unconnected-(P2-Pad135)") (class "Default")
      (node (ref "P2") (pin "135") (pinfunction "135_135") (pintype "passive"))
    )
    (net (code "132") (name "unconnected-(P2-Pad140)") (class "Default")
      (node (ref "P2") (pin "140") (pinfunction "140_140") (pintype "passive"))
    )
    (net (code "133") (name "unconnected-(P2-Pad141)") (class "Default")
      (node (ref "P2") (pin "141") (pinfunction "141_141") (pintype "passive"))
    )
    (net (code "134") (name "unconnected-(P2-Pad142)") (class "Default")
      (node (ref "P2") (pin "142") (pinfunction "142_142") (pintype "passive"))
    )
    (net (code "135") (name "unconnected-(P2-Pad143)") (class "Default")
      (node (ref "P2") (pin "143") (pinfunction "143_143") (pintype "passive"))
    )
    (net (code "136") (name "unconnected-(P2-Pad144)") (class "Default")
      (node (ref "P2") (pin "144") (pinfunction "144_144") (pintype "passive"))
    )
    (net (code "137") (name "unconnected-(P2-Pad145)") (class "Default")
      (node (ref "P2") (pin "145") (pinfunction "145_145") (pintype "passive"))
    )
    (net (code "138") (name "unconnected-(P2-Pad146)") (class "Default")
      (node (ref "P2") (pin "146") (pinfunction "146_146") (pintype "passive"))
    )
    (net (code "139") (name "unconnected-(P2-Pad147)") (class "Default")
      (node (ref "P2") (pin "147") (pinfunction "147_147") (pintype "passive"))
    )
    (net (code "140") (name "unconnected-(P2-Pad148)") (class "Default")
      (node (ref "P2") (pin "148") (pinfunction "148_148") (pintype "passive"))
    )
    (net (code "141") (name "unconnected-(P2-Pad149)") (class "Default")
      (node (ref "P2") (pin "149") (pinfunction "149_149") (pintype "passive"))
    )
    (net (code "142") (name "unconnected-(P2-Pad150)") (class "Default")
      (node (ref "P2") (pin "150") (pinfunction "150_150") (pintype "passive"))
    )
    (net (code "143") (name "unconnected-(P2-Pad152)") (class "Default")
      (node (ref "P2") (pin "152") (pinfunction "152_152") (pintype "passive"))
    )
    (net (code "144") (name "unconnected-(P2-Pad153)") (class "Default")
      (node (ref "P2") (pin "153") (pinfunction "153_153") (pintype "passive"))
    )
    (net (code "145") (name "unconnected-(P2-Pad154)") (class "Default")
      (node (ref "P2") (pin "154") (pinfunction "154_154") (pintype "passive"))
    )
    (net (code "146") (name "unconnected-(P2-Pad155)") (class "Default")
      (node (ref "P2") (pin "155") (pinfunction "155_155") (pintype "passive"))
    )
    (net (code "147") (name "unconnected-(P2-Pad156)") (class "Default")
      (node (ref "P2") (pin "156") (pinfunction "156_156") (pintype "passive"))
    )
    (net (code "148") (name "unconnected-(P2-Pad159)") (class "Default")
      (node (ref "P2") (pin "159") (pinfunction "159_159") (pintype "passive"))
    )
    (net (code "149") (name "unconnected-(P2-Pad236)") (class "Default")
      (node (ref "P2") (pin "236") (pinfunction "236_236") (pintype "passive"))
    )
    (net (code "150") (name "unconnected-(P2-Pad237)") (class "Default")
      (node (ref "P2") (pin "237") (pinfunction "237_237") (pintype "passive"))
    )
    (net (code "151") (name "unconnected-(P2-Pad238)") (class "Default")
      (node (ref "P2") (pin "238") (pinfunction "238_238") (pintype "passive"))
    )
    (net (code "152") (name "unconnected-(P2-Pad239)") (class "Default")
      (node (ref "P2") (pin "239") (pinfunction "239_239") (pintype "passive"))
    )
    (net (code "153") (name "unconnected-(P2-Pad240)") (class "Default")
      (node (ref "P2") (pin "240") (pinfunction "240_240") (pintype "passive"))
    )
    (net (code "154") (name "unconnected-(P2-Pad241)") (class "Default")
      (node (ref "P2") (pin "241") (pinfunction "241_241") (pintype "passive"))
    )
    (net (code "155") (name "unconnected-(P2-Pad242)") (class "Default")
      (node (ref "P2") (pin "242") (pinfunction "242_242") (pintype "passive"))
    )
  )
)
